# Headers.net
KiCad netlist of a schematic drawn in Altium Designer
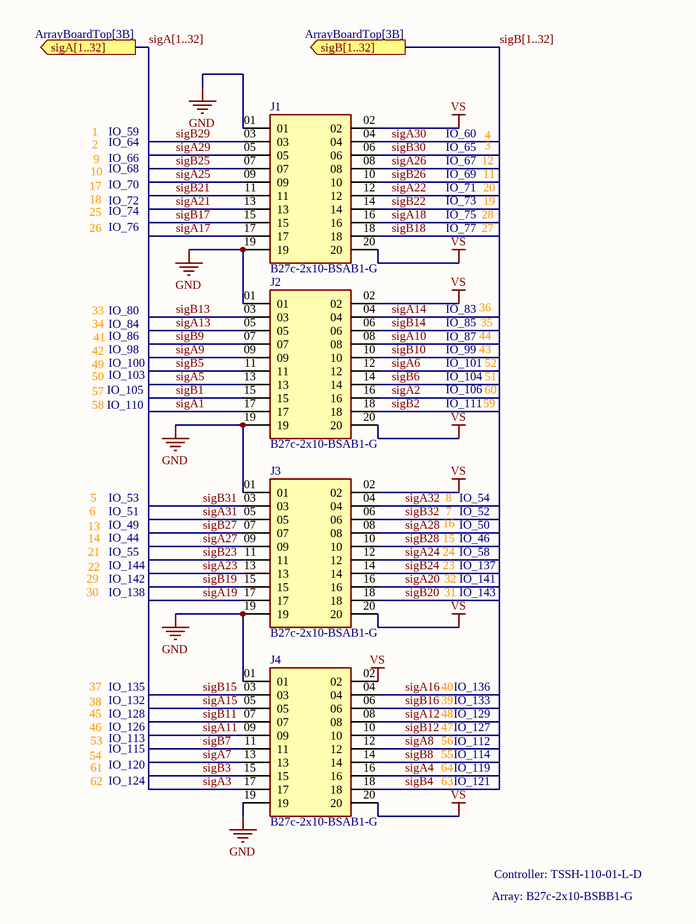
[diagram p0: Headers.SchDoc]

(export (version "E")
  (design (tool "Eeschema 10.0.6"))
  (components
    (comp (ref "J1")
      (value "B27c-2x10-BSAB1-G")
      (footprint "B27C SMT2x10")
      (libsource (lib "InteractLab") (part "B27c-2x10-BSAB1-G"))
    )
    (comp (ref "J2")
      (value "B27c-2x10-BSAB1-G")
      (footprint "B27C SMT2x10")
      (libsource (lib "InteractLab") (part "B27c-2x10-BSAB1-G"))
    )
    (comp (ref "J3")
      (value "B27c-2x10-BSAB1-G")
      (footprint "B27C SMT2x10")
      (libsource (lib "InteractLab") (part "B27c-2x10-BSAB1-G"))
    )
    (comp (ref "J4")
      (value "B27c-2x10-BSAB1-G")
      (footprint "B27C SMT2x10")
      (libsource (lib "InteractLab") (part "B27c-2x10-BSAB1-G"))
    )
  )
  (nets
    (net (code "1") (name "/sigA1") (class "Default")
      (node (ref "J2") (pin "17") (pinfunction "17_17") (pintype "passive"))
    )
    (net (code "2") (name "/sigA2") (class "Default")
      (node (ref "J2") (pin "16") (pinfunction "16_16") (pintype "passive"))
    )
    (net (code "3") (name "/sigA3") (class "Default")
      (node (ref "J4") (pin "17") (pinfunction "17_17") (pintype "passive"))
    )
    (net (code "4") (name "/sigA4") (class "Default")
      (node (ref "J4") (pin "16") (pinfunction "16_16") (pintype "passive"))
    )
    (net (code "5") (name "/sigA5") (class "Default")
      (node (ref "J2") (pin "13") (pinfunction "13_13") (pintype "passive"))
    )
    (net (code "6") (name "/sigA6") (class "Default")
      (node (ref "J2") (pin "12") (pinfunction "12_12") (pintype "passive"))
    )
    (net (code "7") (name "/sigA7") (class "Default")
      (node (ref "J4") (pin "13") (pinfunction "13_13") (pintype "passive"))
    )
    (net (code "8") (name "/sigA8") (class "Default")
      (node (ref "J4") (pin "12") (pinfunction "12_12") (pintype "passive"))
    )
    (net (code "9") (name "/sigA9") (class "Default")
      (node (ref "J2") (pin "09") (pinfunction "09_09") (pintype "passive"))
    )
    (net (code "10") (name "/sigA10") (class "Default")
      (node (ref "J2") (pin "08") (pinfunction "08_08") (pintype "passive"))
    )
    (net (code "11") (name "/sigA11") (class "Default")
      (node (ref "J4") (pin "09") (pinfunction "09_09") (pintype "passive"))
    )
    (net (code "12") (name "/sigA12") (class "Default")
      (node (ref "J4") (pin "08") (pinfunction "08_08") (pintype "passive"))
    )
    (net (code "13") (name "/sigA13") (class "Default")
      (node (ref "J2") (pin "05") (pinfunction "05_05") (pintype "passive"))
    )
    (net (code "14") (name "/sigA14") (class "Default")
      (node (ref "J2") (pin "04") (pinfunction "04_04") (pintype "passive"))
    )
    (net (code "15") (name "/sigA15") (class "Default")
      (node (ref "J4") (pin "05") (pinfunction "05_05") (pintype "passive"))
    )
    (net (code "16") (name "/sigA16") (class "Default")
      (node (ref "J4") (pin "04") (pinfunction "04_04") (pintype "passive"))
    )
    (net (code "17") (name "/sigA17") (class "Default")
      (node (ref "J1") (pin "17") (pinfunction "17_17") (pintype "passive"))
    )
    (net (code "18") (name "/sigA18") (class "Default")
      (node (ref "J1") (pin "16") (pinfunction "16_16") (pintype "passive"))
    )
    (net (code "19") (name "/sigA19") (class "Default")
      (node (ref "J3") (pin "17") (pinfunction "17_17") (pintype "passive"))
    )
    (net (code "20") (name "/sigA20") (class "Default")
      (node (ref "J3") (pin "16") (pinfunction "16_16") (pintype "passive"))
    )
    (net (code "21") (name "/sigA21") (class "Default")
      (node (ref "J1") (pin "13") (pinfunction "13_13") (pintype "passive"))
    )
    (net (code "22") (name "/sigA22") (class "Default")
      (node (ref "J1") (pin "12") (pinfunction "12_12") (pintype "passive"))
    )
    (net (code "23") (name "/sigA23") (class "Default")
      (node (ref "J3") (pin "13") (pinfunction "13_13") (pintype "passive"))
    )
    (net (code "24") (name "/sigA24") (class "Default")
      (node (ref "J3") (pin "12") (pinfunction "12_12") (pintype "passive"))
    )
    (net (code "25") (name "/sigA25") (class "Default")
      (node (ref "J1") (pin "09") (pinfunction "09_09") (pintype "passive"))
    )
    (net (code "26") (name "/sigA26") (class "Default")
      (node (ref "J1") (pin "08") (pinfunction "08_08") (pintype "passive"))
    )
    (net (code "27") (name "/sigA27") (class "Default")
      (node (ref "J3") (pin "09") (pinfunction "09_09") (pintype "passive"))
    )
    (net (code "28") (name "/sigA28") (class "Default")
      (node (ref "J3") (pin "08") (pinfunction "08_08") (pintype "passive"))
    )
    (net (code "29") (name "/sigA29") (class "Default")
      (node (ref "J1") (pin "05") (pinfunction "05_05") (pintype "passive"))
    )
    (net (code "30") (name "/sigA30") (class "Default")
      (node (ref "J1") (pin "04") (pinfunction "04_04") (pintype "passive"))
    )
    (net (code "31") (name "/sigA31") (class "Default")
      (node (ref "J3") (pin "05") (pinfunction "05_05") (pintype "passive"))
    )
    (net (code "32") (name "/sigA32") (class "Default")
      (node (ref "J3") (pin "04") (pinfunction "04_04") (pintype "passive"))
    )
    (net (code "34") (name "/sigB1") (class "Default")
      (node (ref "J2") (pin "15") (pinfunction "15_15") (pintype "passive"))
    )
    (net (code "35") (name "/sigB2") (class "Default")
      (node (ref "J2") (pin "18") (pinfunction "18_18") (pintype "passive"))
    )
    (net (code "36") (name "/sigB3") (class "Default")
      (node (ref "J4") (pin "15") (pinfunction "15_15") (pintype "passive"))
    )
    (net (code "37") (name "/sigB4") (class "Default")
      (node (ref "J4") (pin "18") (pinfunction "18_18") (pintype "passive"))
    )
    (net (code "38") (name "/sigB5") (class "Default")
      (node (ref "J2") (pin "11") (pinfunction "11_11") (pintype "passive"))
    )
    (net (code "39") (name "/sigB6") (class "Default")
      (node (ref "J2") (pin "14") (pinfunction "14_14") (pintype "passive"))
    )
    (net (code "40") (name "/sigB7") (class "Default")
      (node (ref "J4") (pin "11") (pinfunction "11_11") (pintype "passive"))
    )
    (net (code "41") (name "/sigB8") (class "Default")
      (node (ref "J4") (pin "14") (pinfunction "14_14") (pintype "passive"))
    )
    (net (code "42") (name "/sigB9") (class "Default")
      (node (ref "J2") (pin "07") (pinfunction "07_07") (pintype "passive"))
    )
    (net (code "43") (name "/sigB10") (class "Default")
      (node (ref "J2") (pin "10") (pinfunction "10_10") (pintype "passive"))
    )
    (net (code "44") (name "/sigB11") (class "Default")
      (node (ref "J4") (pin "07") (pinfunction "07_07") (pintype "passive"))
    )
    (net (code "45") (name "/sigB12") (class "Default")
      (node (ref "J4") (pin "10") (pinfunction "10_10") (pintype "passive"))
    )
    (net (code "46") (name "/sigB13") (class "Default")
      (node (ref "J2") (pin "03") (pinfunction "03_03") (pintype "passive"))
    )
    (net (code "47") (name "/sigB14") (class "Default")
      (node (ref "J2") (pin "06") (pinfunction "06_06") (pintype "passive"))
    )
    (net (code "48") (name "/sigB15") (class "Default")
      (node (ref "J4") (pin "03") (pinfunction "03_03") (pintype "passive"))
    )
    (net (code "49") (name "/sigB16") (class "Default")
      (node (ref "J4") (pin "06") (pinfunction "06_06") (pintype "passive"))
    )
    (net (code "50") (name "/sigB17") (class "Default")
      (node (ref "J1") (pin "15") (pinfunction "15_15") (pintype "passive"))
    )
    (net (code "51") (name "/sigB18") (class "Default")
      (node (ref "J1") (pin "18") (pinfunction "18_18") (pintype "passive"))
    )
    (net (code "52") (name "/sigB19") (class "Default")
      (node (ref "J3") (pin "15") (pinfunction "15_15") (pintype "passive"))
    )
    (net (code "53") (name "/sigB20") (class "Default")
      (node (ref "J3") (pin "18") (pinfunction "18_18") (pintype "passive"))
    )
    (net (code "54") (name "/sigB21") (class "Default")
      (node (ref "J1") (pin "11") (pinfunction "11_11") (pintype "passive"))
    )
    (net (code "55") (name "/sigB22") (class "Default")
      (node (ref "J1") (pin "14") (pinfunction "14_14") (pintype "passive"))
    )
    (net (code "56") (name "/sigB23") (class "Default")
      (node (ref "J3") (pin "11") (pinfunction "11_11") (pintype "passive"))
    )
    (net (code "57") (name "/sigB24") (class "Default")
      (node (ref "J3") (pin "14") (pinfunction "14_14") (pintype "passive"))
    )
    (net (code "58") (name "/sigB25") (class "Default")
      (node (ref "J1") (pin "07") (pinfunction "07_07") (pintype "passive"))
    )
    (net (code "59") (name "/sigB26") (class "Default")
      (node (ref "J1") (pin "10") (pinfunction "10_10") (pintype "passive"))
    )
    (net (code "60") (name "/sigB27") (class "Default")
      (node (ref "J3") (pin "07") (pinfunction "07_07") (pintype "passive"))
    )
    (net (code "61") (name "/sigB28") (class "Default")
      (node (ref "J3") (pin "10") (pinfunction "10_10") (pintype "passive"))
    )
    (net (code "62") (name "/sigB29") (class "Default")
      (node (ref "J1") (pin "03") (pinfunction "03_03") (pintype "passive"))
    )
    (net (code "63") (name "/sigB30") (class "Default")
      (node (ref "J1") (pin "06") (pinfunction "06_06") (pintype "passive"))
    )
    (net (code "64") (name "/sigB31") (class "Default")
      (node (ref "J3") (pin "03") (pinfunction "03_03") (pintype "passive"))
    )
    (net (code "65") (name "/sigB32") (class "Default")
      (node (ref "J3") (pin "06") (pinfunction "06_06") (pintype "passive"))
    )
    (net (code "67") (name "GND") (class "Default")
      (node (ref "J1") (pin "01") (pinfunction "01_01") (pintype "passive"))
      (node (ref "J1") (pin "19") (pinfunction "19_19") (pintype "passive"))
      (node (ref "J2") (pin "01") (pinfunction "01_01") (pintype "passive"))
      (node (ref "J2") (pin "19") (pinfunction "19_19") (pintype "passive"))
      (node (ref "J3") (pin "01") (pinfunction "01_01") (pintype "passive"))
      (node (ref "J3") (pin "19") (pinfunction "19_19") (pintype "passive"))
      (node (ref "J4") (pin "01") (pinfunction "01_01") (pintype "passive"))
      (node (ref "J4") (pin "19") (pinfunction "19_19") (pintype "passive"))
    )
    (net (code "68") (name "VS") (class "Default")
      (node (ref "J1") (pin "02") (pinfunction "02_02") (pintype "passive"))
      (node (ref "J1") (pin "20") (pinfunction "20_20") (pintype "passive"))
      (node (ref "J2") (pin "02") (pinfunction "02_02") (pintype "passive"))
      (node (ref "J2") (pin "20") (pinfunction "20_20") (pintype "passive"))
      (node (ref "J3") (pin "02") (pinfunction "02_02") (pintype "passive"))
      (node (ref "J3") (pin "20") (pinfunction "20_20") (pintype "passive"))
      (node (ref "J4") (pin "02") (pinfunction "02_02") (pintype "passive"))
      (node (ref "J4") (pin "20") (pinfunction "20_20") (pintype "passive"))
    )
  )
)
